# smd-v5.net
KiCad netlist of a schematic drawn in EAGLE
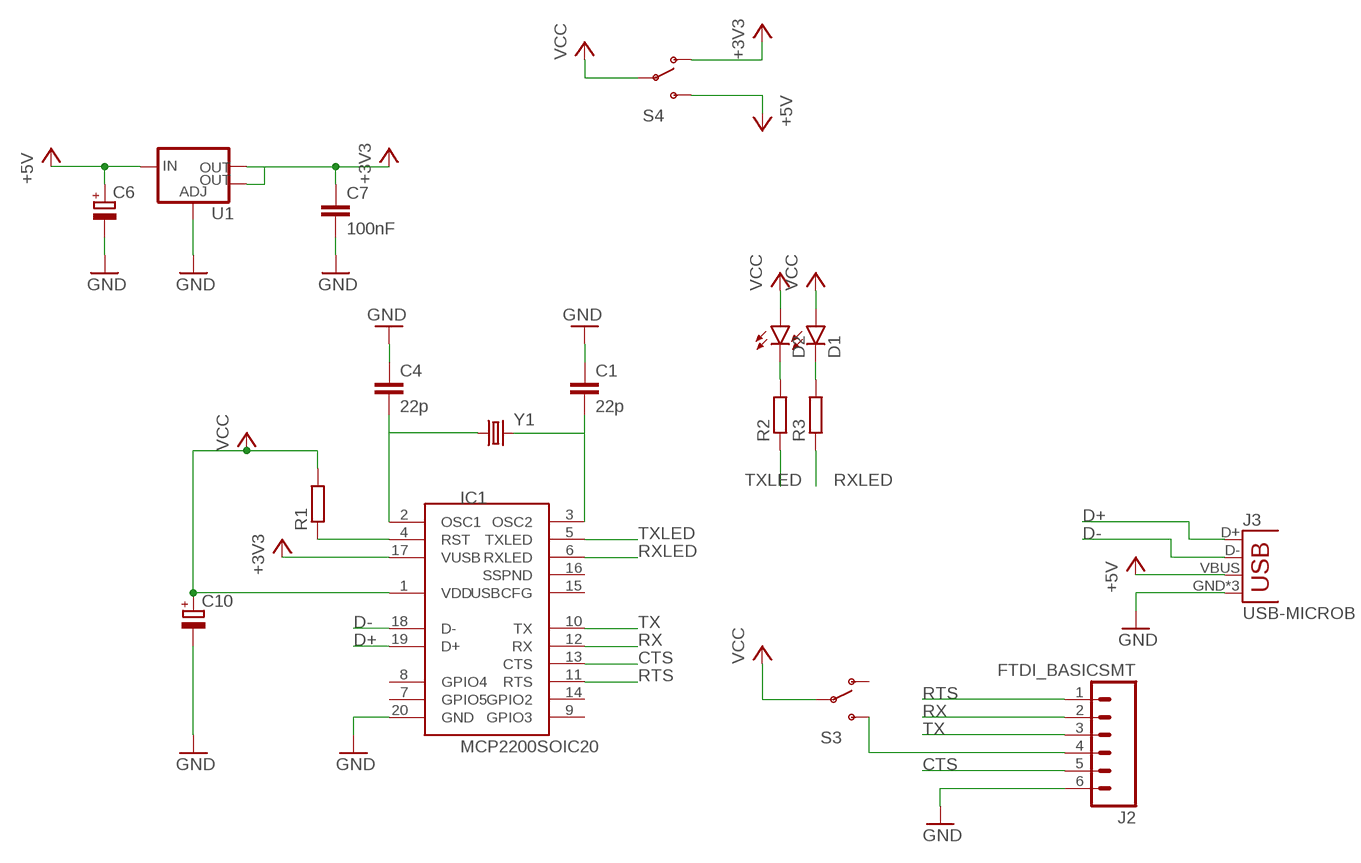
[diagram p0: schematic, sheet 1]

(export (version "E")
  (design (tool "Eeschema 10.0.6"))
  (components
    (comp (ref "C1")
      (value "22p")
      (footprint "eagle-import:C1206K")
      (libsource (lib "eagle-import") (part "C-EUC1206K"))
    )
    (comp (ref "C4")
      (value "22p")
      (footprint "eagle-import:C1206K")
      (libsource (lib "eagle-import") (part "C-EUC1206K"))
    )
    (comp (ref "C6")
      (value "CPOL-EUCT3528")
      (footprint "eagle-import:CT3528")
      (libsource (lib "eagle-import") (part "CPOL-EUCT3528"))
    )
    (comp (ref "C7")
      (value "100nF")
      (footprint "eagle-import:C1206K")
      (libsource (lib "eagle-import") (part "C-EUC1206K"))
    )
    (comp (ref "C10")
      (value "CPOL-EUCT3528")
      (footprint "eagle-import:CT3528")
      (libsource (lib "eagle-import") (part "CPOL-EUCT3528"))
    )
    (comp (ref "D1")
      (value "LED1206")
      (footprint "eagle-import:LED-1206")
      (libsource (lib "eagle-import") (part "LED1206"))
    )
    (comp (ref "D2")
      (value "LED1206")
      (footprint "eagle-import:LED-1206")
      (libsource (lib "eagle-import") (part "LED1206"))
    )
    (comp (ref "IC1")
      (value "MCP2200SOIC20")
      (footprint "eagle-import:SOIC20")
      (libsource (lib "eagle-import") (part "MCP2200SOIC20"))
    )
    (comp (ref "J2")
      (value "FTDI_BASICSMT")
      (footprint "eagle-import:FTDI_DEVICE_RA_SMT_NOHOLES")
      (libsource (lib "eagle-import") (part "FTDI_BASICSMT"))
    )
    (comp (ref "J3")
      (value "USB-MICROB")
      (footprint "eagle-import:USB-MICROB")
      (libsource (lib "eagle-import") (part "USB-MICROB"))
    )
    (comp (ref "R1")
      (value "R-EU_M1206")
      (footprint "eagle-import:M1206")
      (libsource (lib "eagle-import") (part "R-EU_M1206"))
    )
    (comp (ref "R2")
      (value "R-EU_M1206")
      (footprint "eagle-import:M1206")
      (libsource (lib "eagle-import") (part "R-EU_M1206"))
    )
    (comp (ref "R3")
      (value "R-EU_M1206")
      (footprint "eagle-import:M1206")
      (libsource (lib "eagle-import") (part "R-EU_M1206"))
    )
    (comp (ref "S3")
      (value "SWITCH-SPDT-SMD-A")
      (footprint "eagle-import:SWITCH-SPST-SMD-A")
      (libsource (lib "eagle-import") (part "SWITCH-SPDT-SMD-A"))
    )
    (comp (ref "S4")
      (value "SWITCH-SPDT-SMD-A")
      (footprint "eagle-import:SWITCH-SPST-SMD-A")
      (libsource (lib "eagle-import") (part "SWITCH-SPDT-SMD-A"))
    )
    (comp (ref "U1")
      (value "V_REG_LM1117SOT223")
      (footprint "eagle-import:SOT223")
      (libsource (lib "eagle-import") (part "V_REG_LM1117SOT223"))
    )
    (comp (ref "Y1")
      (value "CRYSTALSMD")
      (footprint "eagle-import:HC49UP")
      (libsource (lib "eagle-import") (part "CRYSTALSMD"))
    )
  )
  (nets
    (net (code "1") (name "+3V3") (class "Default")
      (node (ref "C7") (pin "1") (pinfunction "1_1") (pintype "passive"))
      (node (ref "IC1") (pin "17") (pinfunction "VUSB_17") (pintype "bidirectional"))
      (node (ref "S4") (pin "1") (pinfunction "O_1") (pintype "passive"))
      (node (ref "U1") (pin "2") (pinfunction "OUT_2") (pintype "output"))
      (node (ref "U1") (pin "4") (pinfunction "OUT_4") (pintype "output"))
    )
    (net (code "2") (name "+5V") (class "Default")
      (node (ref "C6") (pin "+") (pinfunction "+_+") (pintype "passive"))
      (node (ref "J3") (pin "VBUS") (pinfunction "VBUS_VBUS") (pintype "bidirectional"))
      (node (ref "S4") (pin "3") (pinfunction "S_3") (pintype "passive"))
      (node (ref "U1") (pin "3") (pinfunction "IN_3") (pintype "input"))
    )
    (net (code "3") (name "/CTS") (class "Default")
      (node (ref "IC1") (pin "13") (pinfunction "CTS_13") (pintype "bidirectional"))
      (node (ref "J2") (pin "5") (pinfunction "5_5") (pintype "passive"))
    )
    (net (code "4") (name "/D+") (class "Default")
      (node (ref "IC1") (pin "19") (pinfunction "D+_19") (pintype "bidirectional"))
      (node (ref "J3") (pin "D+") (pinfunction "D+_D+") (pintype "bidirectional"))
    )
    (net (code "5") (name "/D-") (class "Default")
      (node (ref "IC1") (pin "18") (pinfunction "D-_18") (pintype "bidirectional"))
      (node (ref "J3") (pin "D-") (pinfunction "D-_D-") (pintype "bidirectional"))
    )
    (net (code "6") (name "/RTS") (class "Default")
      (node (ref "IC1") (pin "11") (pinfunction "RTS_11") (pintype "bidirectional"))
      (node (ref "J2") (pin "1") (pinfunction "1_1") (pintype "passive"))
    )
    (net (code "7") (name "/RX") (class "Default")
      (node (ref "IC1") (pin "12") (pinfunction "RX_12") (pintype "bidirectional"))
      (node (ref "J2") (pin "2") (pinfunction "2_2") (pintype "passive"))
    )
    (net (code "8") (name "/RXLED") (class "Default")
      (node (ref "IC1") (pin "6") (pinfunction "RXLED_6") (pintype "bidirectional"))
      (node (ref "R3") (pin "1") (pinfunction "1_1") (pintype "passive"))
    )
    (net (code "9") (name "/TX") (class "Default")
      (node (ref "IC1") (pin "10") (pinfunction "TX_10") (pintype "bidirectional"))
      (node (ref "J2") (pin "3") (pinfunction "3_3") (pintype "passive"))
    )
    (net (code "10") (name "/TXLED") (class "Default")
      (node (ref "IC1") (pin "5") (pinfunction "TXLED_5") (pintype "bidirectional"))
      (node (ref "R2") (pin "1") (pinfunction "1_1") (pintype "passive"))
    )
    (net (code "11") (name "GND") (class "Default")
      (node (ref "C1") (pin "1") (pinfunction "1_1") (pintype "passive"))
      (node (ref "C10") (pin "-") (pinfunction "-_-") (pintype "passive"))
      (node (ref "C4") (pin "1") (pinfunction "1_1") (pintype "passive"))
      (node (ref "C6") (pin "-") (pinfunction "-_-") (pintype "passive"))
      (node (ref "C7") (pin "2") (pinfunction "2_2") (pintype "passive"))
      (node (ref "IC1") (pin "20") (pinfunction "GND_20") (pintype "bidirectional"))
      (node (ref "J2") (pin "6") (pinfunction "6_6") (pintype "passive"))
      (node (ref "J3") (pin "GND") (pinfunction "GND_GND") (pintype "bidirectional"))
      (node (ref "J3") (pin "MT1") (pinfunction "GND_MT1") (pintype "bidirectional"))
      (node (ref "J3") (pin "MT2") (pinfunction "GND_MT2") (pintype "bidirectional"))
      (node (ref "U1") (pin "1") (pinfunction "ADJ_1") (pintype "input"))
    )
    (net (code "12") (name "Net-(D1-PadC)") (class "Default")
      (node (ref "D1") (pin "C") (pinfunction "C_C") (pintype "passive"))
      (node (ref "R3") (pin "2") (pinfunction "2_2") (pintype "passive"))
    )
    (net (code "13") (name "Net-(D2-PadC)") (class "Default")
      (node (ref "D2") (pin "C") (pinfunction "C_C") (pintype "passive"))
      (node (ref "R2") (pin "2") (pinfunction "2_2") (pintype "passive"))
    )
    (net (code "14") (name "Net-(IC1-OSC1)") (class "Default")
      (node (ref "C4") (pin "2") (pinfunction "2_2") (pintype "passive"))
      (node (ref "IC1") (pin "2") (pinfunction "OSC1_2") (pintype "bidirectional"))
      (node (ref "Y1") (pin "1") (pinfunction "1_1") (pintype "passive"))
    )
    (net (code "15") (name "Net-(IC1-OSC2)") (class "Default")
      (node (ref "C1") (pin "2") (pinfunction "2_2") (pintype "passive"))
      (node (ref "IC1") (pin "3") (pinfunction "OSC2_3") (pintype "bidirectional"))
      (node (ref "Y1") (pin "2") (pinfunction "2_2") (pintype "passive"))
    )
    (net (code "16") (name "Net-(IC1-RST)") (class "Default")
      (node (ref "IC1") (pin "4") (pinfunction "RST_4") (pintype "bidirectional"))
      (node (ref "R1") (pin "1") (pinfunction "1_1") (pintype "passive"))
    )
    (net (code "17") (name "Net-(S3-S)") (class "Default")
      (node (ref "J2") (pin "4") (pinfunction "4_4") (pintype "passive"))
      (node (ref "S3") (pin "3") (pinfunction "S_3") (pintype "passive"))
    )
    (net (code "18") (name "VCC") (class "Default")
      (node (ref "C10") (pin "+") (pinfunction "+_+") (pintype "passive"))
      (node (ref "D1") (pin "A") (pinfunction "A_A") (pintype "passive"))
      (node (ref "D2") (pin "A") (pinfunction "A_A") (pintype "passive"))
      (node (ref "IC1") (pin "1") (pinfunction "VDD_1") (pintype "bidirectional"))
      (node (ref "R1") (pin "2") (pinfunction "2_2") (pintype "passive"))
      (node (ref "S3") (pin "2") (pinfunction "P_2") (pintype "passive"))
      (node (ref "S4") (pin "2") (pinfunction "P_2") (pintype "passive"))
    )
    (net (code "19") (name "unconnected-(IC1-GPIO2-Pad14)") (class "Default")
      (node (ref "IC1") (pin "14") (pinfunction "GPIO2_14") (pintype "bidirectional"))
    )
    (net (code "20") (name "unconnected-(IC1-GPIO3-Pad9)") (class "Default")
      (node (ref "IC1") (pin "9") (pinfunction "GPIO3_9") (pintype "bidirectional"))
    )
    (net (code "21") (name "unconnected-(IC1-GPIO4-Pad8)") (class "Default")
      (node (ref "IC1") (pin "8") (pinfunction "GPIO4_8") (pintype "bidirectional"))
    )
    (net (code "22") (name "unconnected-(IC1-GPIO5-Pad7)") (class "Default")
      (node (ref "IC1") (pin "7") (pinfunction "GPIO5_7") (pintype "bidirectional"))
    )
    (net (code "23") (name "unconnected-(IC1-SSPND-Pad16)") (class "Default")
      (node (ref "IC1") (pin "16") (pinfunction "SSPND_16") (pintype "bidirectional"))
    )
    (net (code "24") (name "unconnected-(IC1-USBCFG-Pad15)") (class "Default")
      (node (ref "IC1") (pin "15") (pinfunction "USBCFG_15") (pintype "bidirectional"))
    )
    (net (code "25") (name "unconnected-(S3-O-Pad1)") (class "Default")
      (node (ref "S3") (pin "1") (pinfunction "O_1") (pintype "passive"))
    )
  )
)
